# car_key.net
KiCad netlist of a schematic drawn in EAGLE
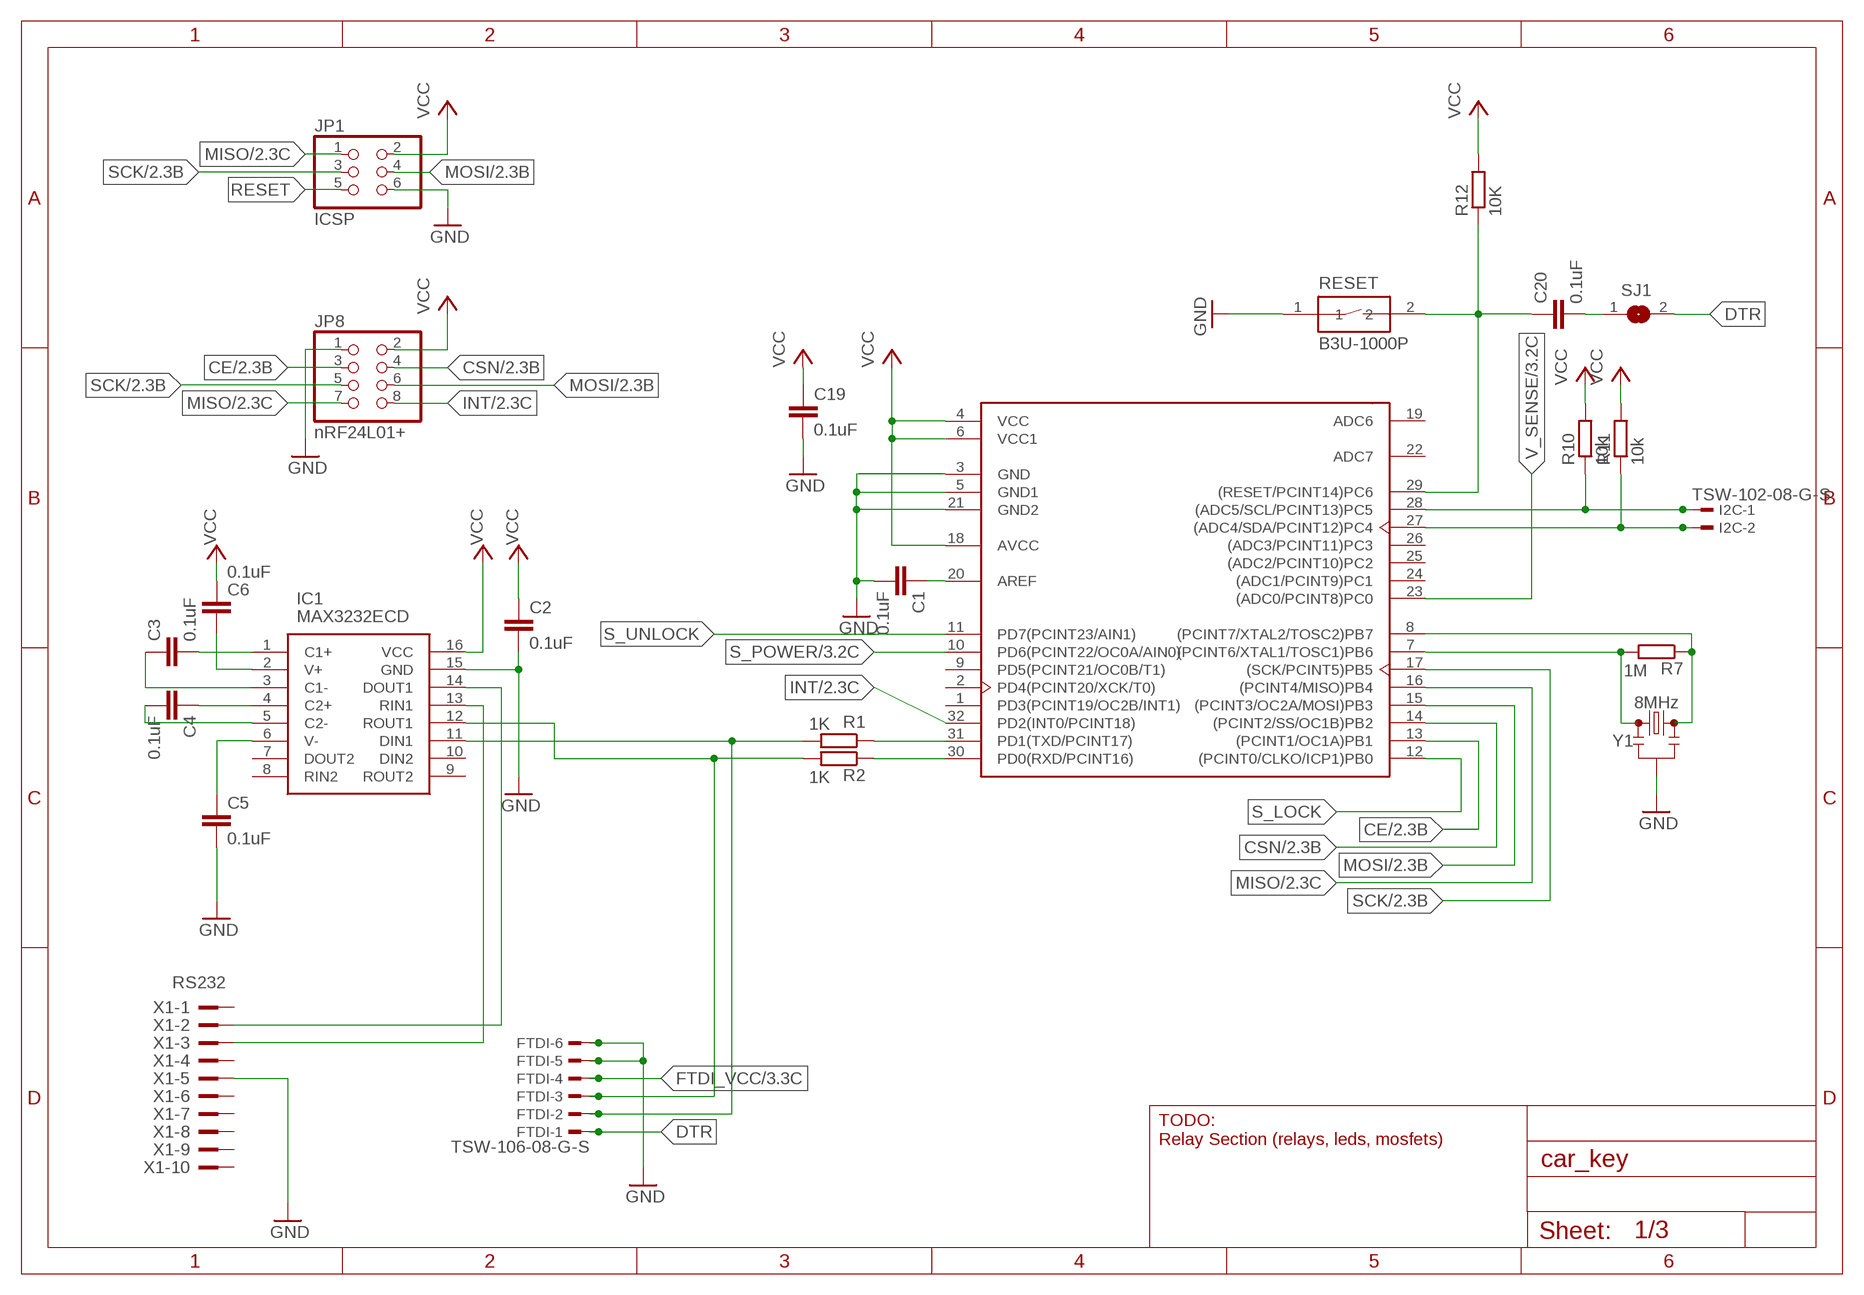
[diagram p0: schematic, sheet 1]
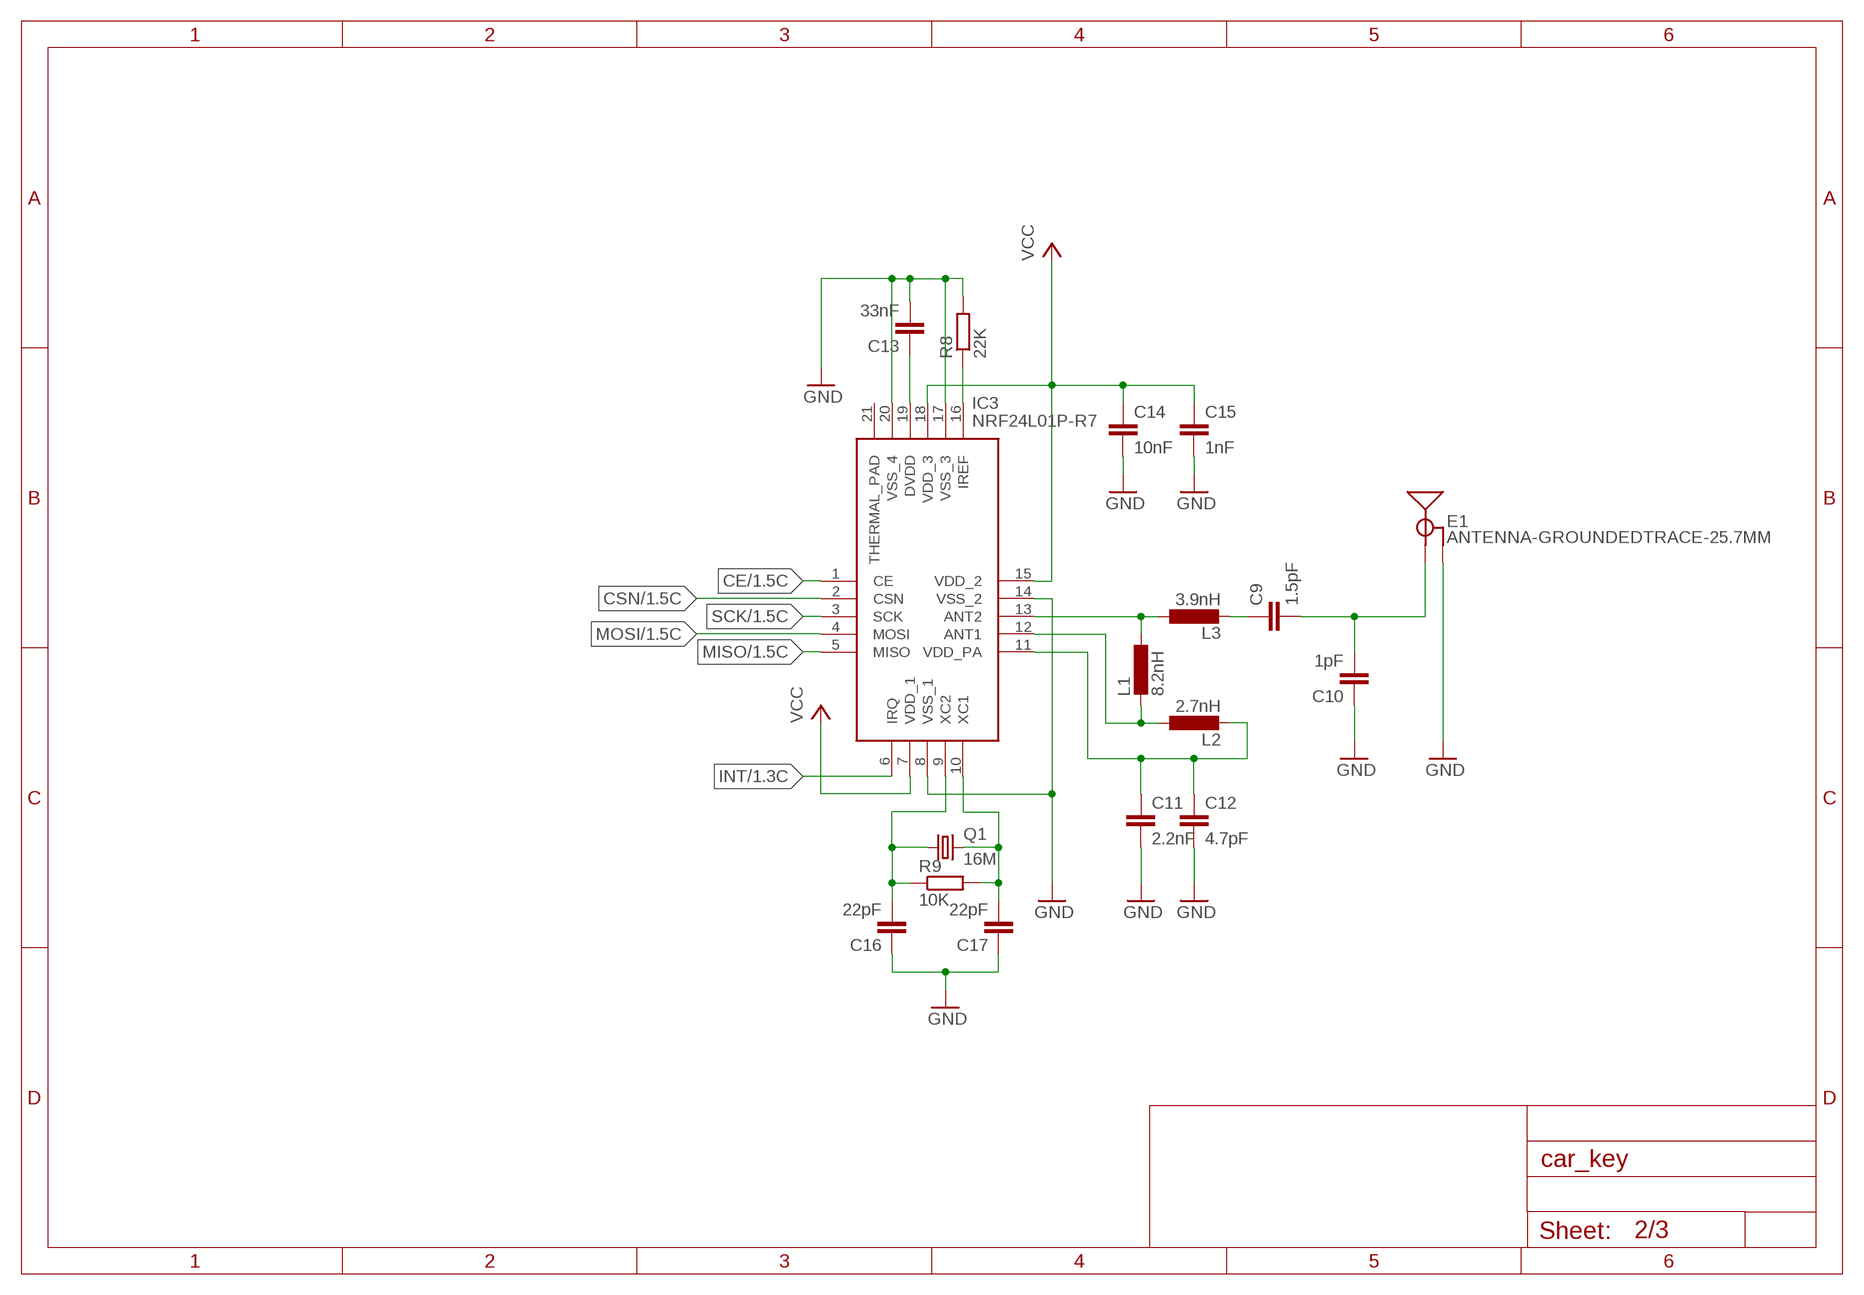
[diagram p1: schematic, sheet 2]
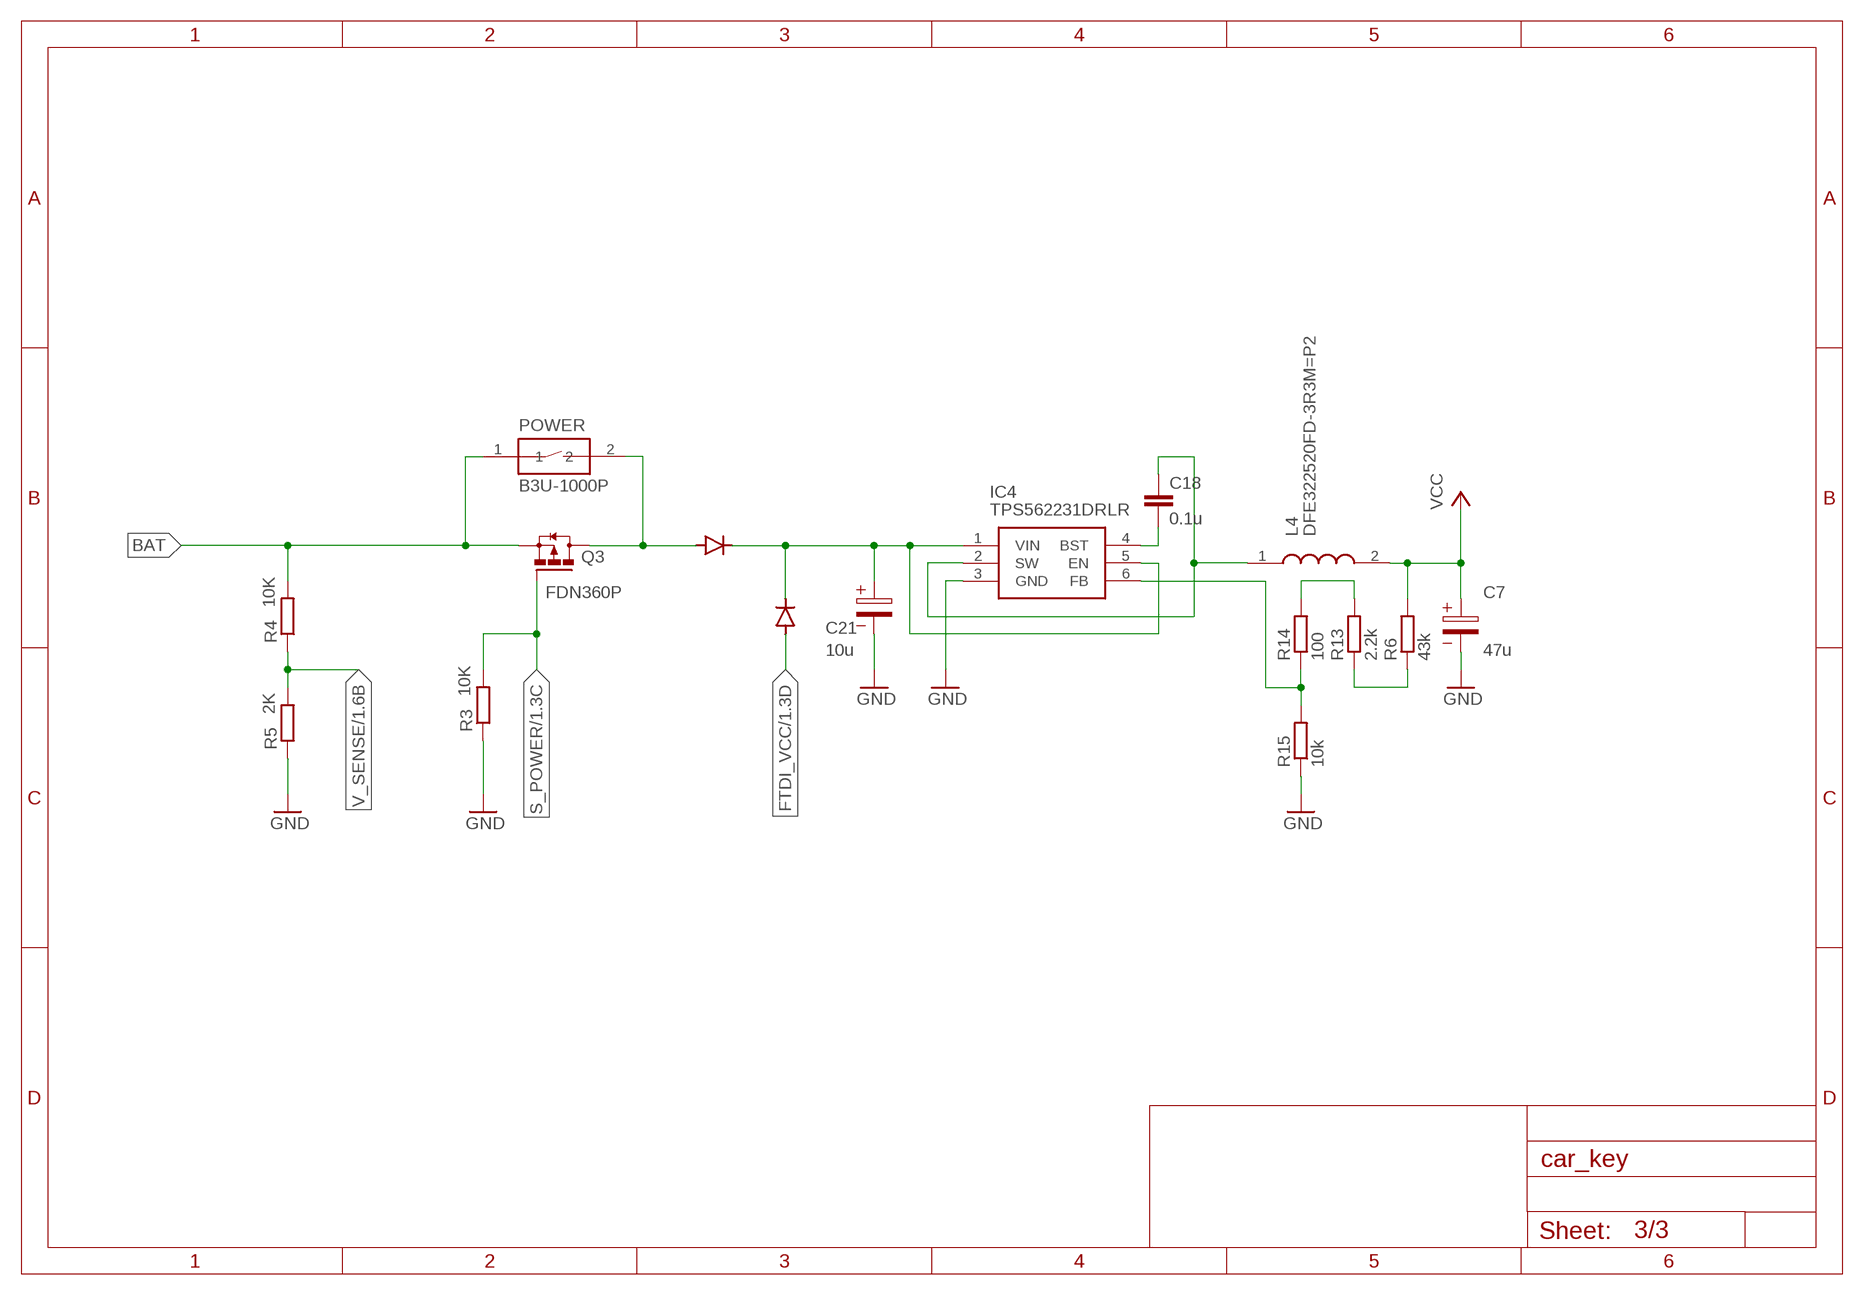
[diagram p2: schematic, sheet 3]

(export (version "E")
  (design (tool "Eeschema 10.0.6"))
  (components
    (comp (ref "C9")
      (value "1.5pF")
      (footprint "eagle-import:C0805")
      (libsource (lib "eagle-import") (part "resistor_348_C-EUC0805"))
    )
    (comp (ref "C10")
      (value "1pF")
      (footprint "eagle-import:C0805")
      (libsource (lib "eagle-import") (part "resistor_348_C-EUC0805"))
    )
    (comp (ref "C11")
      (value "2.2nF")
      (footprint "eagle-import:C0805")
      (libsource (lib "eagle-import") (part "resistor_348_C-EUC0805"))
    )
    (comp (ref "C12")
      (value "4.7pF")
      (footprint "eagle-import:C0805")
      (libsource (lib "eagle-import") (part "resistor_348_C-EUC0805"))
    )
    (comp (ref "C13")
      (value "33nF")
      (footprint "eagle-import:C0805")
      (libsource (lib "eagle-import") (part "resistor_348_C-EUC0805"))
    )
    (comp (ref "C14")
      (value "10nF")
      (footprint "eagle-import:C0805")
      (libsource (lib "eagle-import") (part "resistor_348_C-EUC0805"))
    )
    (comp (ref "C15")
      (value "1nF")
      (footprint "eagle-import:C0805")
      (libsource (lib "eagle-import") (part "resistor_348_C-EUC0805"))
    )
    (comp (ref "C16")
      (value "22pF")
      (footprint "eagle-import:C0805")
      (libsource (lib "eagle-import") (part "resistor_348_C-EUC0805"))
    )
    (comp (ref "C17")
      (value "22pF")
      (footprint "eagle-import:C0805")
      (libsource (lib "eagle-import") (part "resistor_348_C-EUC0805"))
    )
    (comp (ref "E1")
      (value "ANTENNA-GROUNDEDTRACE-25.7MM")
      (footprint "eagle-import:TRACE_ANTENNA_2.4GHZ_25.7MM")
      (libsource (lib "eagle-import") (part "ANTENNA-GROUNDEDTRACE-25.7MM"))
    )
    (comp (ref "IC3")
      (value "NRF24L01P-R7")
      (footprint "eagle-import:QFN50P400X400X95-21N")
      (fields (field (name "MOUSER_PART_NUMBER") "949-NRF24L01P-R7"))
      (libsource (lib "eagle-import") (part "NRF24L01P-R7"))
    )
    (comp (ref "L1")
      (value "8.2nH")
      (footprint "eagle-import:L2012C")
      (libsource (lib "eagle-import") (part "L-EUL2012C"))
    )
    (comp (ref "L2")
      (value "2.7nH")
      (footprint "eagle-import:L2012C")
      (libsource (lib "eagle-import") (part "L-EUL2012C"))
    )
    (comp (ref "L3")
      (value "3.9nH")
      (footprint "eagle-import:L2012C")
      (libsource (lib "eagle-import") (part "L-EUL2012C"))
    )
    (comp (ref "Q1")
      (value "16M")
      (footprint "eagle-import:HC49_S")
      (libsource (lib "eagle-import") (part "CRYSTALHC49S"))
    )
    (comp (ref "R8")
      (value "22K")
      (footprint "eagle-import:R0805")
      (libsource (lib "eagle-import") (part "R-EU_R0805"))
    )
    (comp (ref "R9")
      (value "10K")
      (footprint "eagle-import:R0805")
      (libsource (lib "eagle-import") (part "R-EU_R0805"))
    )
    (comp (ref "C1")
      (value "0.1uF")
      (footprint "eagle-import:C0805")
      (libsource (lib "eagle-import") (part "C-EUC0805"))
    )
    (comp (ref "C2")
      (value "0.1uF")
      (footprint "eagle-import:C0805")
      (libsource (lib "eagle-import") (part "C-EUC0805"))
    )
    (comp (ref "C3")
      (value "0.1uF")
      (footprint "eagle-import:C0805")
      (libsource (lib "eagle-import") (part "C-EUC0805"))
    )
    (comp (ref "C4")
      (value "0.1uF")
      (footprint "eagle-import:C0805")
      (libsource (lib "eagle-import") (part "C-EUC0805"))
    )
    (comp (ref "C5")
      (value "0.1uF")
      (footprint "eagle-import:C0805")
      (libsource (lib "eagle-import") (part "C-EUC0805"))
    )
    (comp (ref "C6")
      (value "0.1uF")
      (footprint "eagle-import:C0805")
      (libsource (lib "eagle-import") (part "C-EUC0805"))
    )
    (comp (ref "C19")
      (value "0.1uF")
      (footprint "eagle-import:C0805")
      (libsource (lib "eagle-import") (part "C-EUC0805"))
    )
    (comp (ref "C20")
      (value "0.1uF")
      (footprint "eagle-import:C0805")
      (libsource (lib "eagle-import") (part "C-EUC0805"))
    )
    (comp (ref "FTDI")
      (value "TSW-106-08-G-S")
      (footprint "eagle-import:TSW-106-XX-G-S")
      (fields (field (name "MF") "Samtec Inc.") (field (name "MPN") "TSW-106-07-G-S"))
      (libsource (lib "eagle-import") (part "TSW-106--G-S08"))
    )
    (comp (ref "I2C")
      (value "TSW-102-08-G-S")
      (footprint "eagle-import:TSW-102-XX-G-S")
      (fields (field (name "MF") "Samtec Inc.") (field (name "MPN") "TSW-102-07-G-S"))
      (libsource (lib "eagle-import") (part "TSW-102--G-S08"))
    )
    (comp (ref "IC1")
      (value "MAX3232ECD")
      (footprint "eagle-import:SOIC127P600X175-16N")
      (fields (field (name "MOUSER_PART_NUMBER") "595-MAX3232ECD") (field (name "RS_PART_NUMBER") "6608704P"))
      (libsource (lib "eagle-import") (part "MAX3232ECD"))
    )
    (comp (ref "JP1")
      (value "ICSP")
      (footprint "eagle-import:2X03")
      (libsource (lib "eagle-import") (part "PINHD-2X3"))
    )
    (comp (ref "JP8")
      (value "nRF24L01+")
      (footprint "eagle-import:2X04")
      (libsource (lib "eagle-import") (part "PINHD-2X4"))
    )
    (comp (ref "R1")
      (value "1K")
      (footprint "eagle-import:R0805")
      (libsource (lib "eagle-import") (part "R-EU_R0805"))
    )
    (comp (ref "R2")
      (value "1K")
      (footprint "eagle-import:R0805")
      (libsource (lib "eagle-import") (part "R-EU_R0805"))
    )
    (comp (ref "R7")
      (value "1M")
      (footprint "eagle-import:R0805")
      (libsource (lib "eagle-import") (part "R-EU_R0805"))
    )
    (comp (ref "R10")
      (value "10k")
      (footprint "eagle-import:R0805")
      (libsource (lib "eagle-import") (part "R-EU_R0805"))
    )
    (comp (ref "R11")
      (value "10k")
      (footprint "eagle-import:R0805")
      (libsource (lib "eagle-import") (part "R-EU_R0805"))
    )
    (comp (ref "R12")
      (value "10K")
      (footprint "eagle-import:R0805")
      (libsource (lib "eagle-import") (part "R-EU_R0805"))
    )
    (comp (ref "RESET")
      (value "B3U-1000P")
      (footprint "eagle-import:B3U-1000P")
      (fields
        (field (name "DIGI_KEY_PART_NUMBER") "SW1020CT-ND")
        (field (name "MANUFACTURER") "Omron Electronics Inc-EMC Div")
        (field (name "CREATED_BY") "PCBLayout.com")
      )
      (libsource (lib "eagle-import") (part "B3U-1000P"))
    )
    (comp (ref "SJ1") (value "SJ") (footprint "eagle-import:SJ") (libsource (lib "eagle-import") (part "SJ")))
    (comp (ref "U2")
      (value "ATMEGA328P-AU")
      (footprint "eagle-import:TQFP-32")
      (fields
        (field (name "DIGIKEY_PART_NUMBER") "ATMEGA328P-AU-ND")
        (field (name "MANUFACTURER") "Microchip Technology")
        (field (name "CREATED_BY") "PCBLayout.com")
      )
      (libsource (lib "eagle-import") (part "ATMEGA328P-AU"))
    )
    (comp (ref "X1")
      (value "RS232")
      (footprint "eagle-import:PAK100_2500-10")
      (fields (field (name "MF") "3M") (field (name "MPN") "2510-6002UB"))
      (libsource (lib "eagle-import") (part "2510-"))
    )
    (comp (ref "Y1")
      (value "8MHz")
      (footprint "eagle-import:RESONATOR-SMD-3.2X1.3")
      (libsource (lib "eagle-import") (part "RESONATOR-8MHZSMD_3.2X1.3"))
    )
    (comp (ref "C7")
      (value "47u")
      (footprint "eagle-import:2.6X1.6X1(BXCXA)")
      (libsource (lib "eagle-import") (part "WCAP-ASLI_865080140004_4X5,5"))
    )
    (comp (ref "C18")
      (value "0.1u")
      (footprint "eagle-import:C0805")
      (libsource (lib "eagle-import") (part "C-EUC0805"))
    )
    (comp (ref "C21")
      (value "10u")
      (footprint "eagle-import:2.6X1.6X1(BXCXA)")
      (libsource (lib "eagle-import") (part "WCAP-ASLI_865080340001_4X5,5"))
    )
    (comp (ref "D1")
      (value "DIODE-SOD123")
      (footprint "eagle-import:SOD123")
      (libsource (lib "eagle-import") (part "DIODE-SOD123"))
    )
    (comp (ref "D2")
      (value "DIODE-SOD123")
      (footprint "eagle-import:SOD123")
      (libsource (lib "eagle-import") (part "DIODE-SOD123"))
    )
    (comp (ref "IC4")
      (value "TPS562231DRLR")
      (footprint "eagle-import:SOTFL50P160X60-6N")
      (fields (field (name "MOUSER_PART_NUMBER") "595-TPS562231DRLR"))
      (libsource (lib "eagle-import") (part "TPS562231DRLR"))
    )
    (comp (ref "L4")
      (value "DFE322520FD-3R3M=P2")
      (footprint "eagle-import:INDC3225X200N")
      (fields (field (name "MOUSER_PART_NUMBER") "81-DFE322520FD3R3MP2"))
      (libsource (lib "eagle-import") (part "DFE322520FD-3R3M=P2"))
    )
    (comp (ref "POWER")
      (value "B3U-1000P")
      (footprint "eagle-import:B3U-1000P")
      (fields
        (field (name "DIGI_KEY_PART_NUMBER") "SW1020CT-ND")
        (field (name "MANUFACTURER") "Omron Electronics Inc-EMC Div")
        (field (name "CREATED_BY") "PCBLayout.com")
      )
      (libsource (lib "eagle-import") (part "B3U-1000P"))
    )
    (comp (ref "Q3")
      (value "FDN360P")
      (footprint "eagle-import:SUPER-SOT3")
      (libsource (lib "eagle-import") (part "FDN360P"))
    )
    (comp (ref "R3")
      (value "10K")
      (footprint "eagle-import:R0805")
      (libsource (lib "eagle-import") (part "R-EU_R0805"))
    )
    (comp (ref "R4")
      (value "10K")
      (footprint "eagle-import:R0805")
      (libsource (lib "eagle-import") (part "R-EU_R0805"))
    )
    (comp (ref "R5")
      (value "2K")
      (footprint "eagle-import:R0805")
      (libsource (lib "eagle-import") (part "R-EU_R0805"))
    )
    (comp (ref "R6")
      (value "43k")
      (footprint "eagle-import:R0805")
      (libsource (lib "eagle-import") (part "R-EU_R0805"))
    )
    (comp (ref "R13")
      (value "2.2k")
      (footprint "eagle-import:R0805")
      (libsource (lib "eagle-import") (part "R-EU_R0805"))
    )
    (comp (ref "R14")
      (value "100")
      (footprint "eagle-import:R0805")
      (libsource (lib "eagle-import") (part "R-EU_R0805"))
    )
    (comp (ref "R15")
      (value "10k")
      (footprint "eagle-import:R0805")
      (libsource (lib "eagle-import") (part "R-EU_R0805"))
    )
  )
  (nets
    (net (code "1") (name "BAT") (class "Default")
      (node (ref "POWER") (pin "1") (pinfunction "1_1") (pintype "passive"))
      (node (ref "Q3") (pin "2") (pinfunction "S_2") (pintype "passive"))
      (node (ref "R4") (pin "2") (pinfunction "2_2") (pintype "passive"))
    )
    (net (code "2") (name "CE") (class "Default")
      (node (ref "IC3") (pin "1") (pinfunction "CE_1") (pintype "bidirectional"))
      (node (ref "JP8") (pin "3") (pinfunction "3_3") (pintype "passive"))
      (node (ref "U2") (pin "13") (pinfunction "(PCINT1/OC1A)PB1_13") (pintype "bidirectional"))
    )
    (net (code "3") (name "CSN") (class "Default")
      (node (ref "IC3") (pin "2") (pinfunction "CSN_2") (pintype "bidirectional"))
      (node (ref "JP8") (pin "4") (pinfunction "4_4") (pintype "passive"))
      (node (ref "U2") (pin "14") (pinfunction "(PCINT2/SS/OC1B)PB2_14") (pintype "bidirectional"))
    )
    (net (code "4") (name "DTR") (class "Default")
      (node (ref "FTDI") (pin "1") (pinfunction "1_1") (pintype "passive"))
      (node (ref "SJ1") (pin "2") (pinfunction "2_2") (pintype "passive"))
    )
    (net (code "5") (name "FTDI_VCC") (class "Default")
      (node (ref "D1") (pin "A") (pinfunction "A_A") (pintype "passive"))
      (node (ref "FTDI") (pin "4") (pinfunction "1_4") (pintype "passive"))
    )
    (net (code "6") (name "GND") (class "Default")
      (node (ref "C1") (pin "2") (pinfunction "2_2") (pintype "passive"))
      (node (ref "C10") (pin "1") (pinfunction "1_1") (pintype "passive"))
      (node (ref "C11") (pin "2") (pinfunction "2_2") (pintype "passive"))
      (node (ref "C12") (pin "2") (pinfunction "2_2") (pintype "passive"))
      (node (ref "C13") (pin "2") (pinfunction "2_2") (pintype "passive"))
      (node (ref "C14") (pin "2") (pinfunction "2_2") (pintype "passive"))
      (node (ref "C15") (pin "2") (pinfunction "2_2") (pintype "passive"))
      (node (ref "C16") (pin "1") (pinfunction "1_1") (pintype "passive"))
      (node (ref "C17") (pin "1") (pinfunction "1_1") (pintype "passive"))
      (node (ref "C19") (pin "2") (pinfunction "2_2") (pintype "passive"))
      (node (ref "C2") (pin "2") (pinfunction "2_2") (pintype "passive"))
      (node (ref "C21") (pin "2") (pinfunction "2_2") (pintype "passive"))
      (node (ref "C5") (pin "2") (pinfunction "2_2") (pintype "passive"))
      (node (ref "C7") (pin "2") (pinfunction "2_2") (pintype "passive"))
      (node (ref "E1") (pin "GND") (pinfunction "GND_GND") (pintype "bidirectional"))
      (node (ref "E1") (pin "GND2") (pinfunction "GND_GND2") (pintype "bidirectional"))
      (node (ref "FTDI") (pin "5") (pinfunction "1_5") (pintype "passive"))
      (node (ref "FTDI") (pin "6") (pinfunction "1_6") (pintype "passive"))
      (node (ref "IC1") (pin "15") (pinfunction "GND_15") (pintype "bidirectional"))
      (node (ref "IC3") (pin "14") (pinfunction "VSS_2_14") (pintype "bidirectional"))
      (node (ref "IC3") (pin "17") (pinfunction "VSS_3_17") (pintype "bidirectional"))
      (node (ref "IC3") (pin "20") (pinfunction "VSS_4_20") (pintype "bidirectional"))
      (node (ref "IC3") (pin "8") (pinfunction "VSS_1_8") (pintype "bidirectional"))
      (node (ref "IC4") (pin "3") (pinfunction "GND_3") (pintype "bidirectional"))
      (node (ref "JP1") (pin "6") (pinfunction "6_6") (pintype "passive"))
      (node (ref "JP8") (pin "1") (pinfunction "1_1") (pintype "passive"))
      (node (ref "R15") (pin "1") (pinfunction "1_1") (pintype "passive"))
      (node (ref "R3") (pin "1") (pinfunction "1_1") (pintype "passive"))
      (node (ref "R5") (pin "1") (pinfunction "1_1") (pintype "passive"))
      (node (ref "R8") (pin "2") (pinfunction "2_2") (pintype "passive"))
      (node (ref "RESET") (pin "1") (pinfunction "1_1") (pintype "passive"))
      (node (ref "U2") (pin "21") (pinfunction "GND2_21") (pintype "power_in"))
      (node (ref "U2") (pin "3") (pinfunction "GND_3") (pintype "power_in"))
      (node (ref "U2") (pin "5") (pinfunction "GND1_5") (pintype "power_in"))
      (node (ref "X1") (pin "5") (pinfunction "KL_5") (pintype "passive"))
      (node (ref "Y1") (pin "2") (pinfunction "2_2") (pintype "passive"))
    )
    (net (code "7") (name "INT") (class "Default")
      (node (ref "IC3") (pin "6") (pinfunction "IRQ_6") (pintype "bidirectional"))
      (node (ref "JP8") (pin "8") (pinfunction "8_8") (pintype "passive"))
      (node (ref "U2") (pin "32") (pinfunction "PD2(INT0/PCINT18)_32") (pintype "bidirectional"))
    )
    (net (code "8") (name "MISO") (class "Default")
      (node (ref "IC3") (pin "5") (pinfunction "MISO_5") (pintype "bidirectional"))
      (node (ref "JP1") (pin "1") (pinfunction "1_1") (pintype "passive"))
      (node (ref "JP8") (pin "7") (pinfunction "7_7") (pintype "passive"))
      (node (ref "U2") (pin "16") (pinfunction "(PCINT4/MISO)PB4_16") (pintype "bidirectional"))
    )
    (net (code "9") (name "MOSI") (class "Default")
      (node (ref "IC3") (pin "4") (pinfunction "MOSI_4") (pintype "bidirectional"))
      (node (ref "JP1") (pin "4") (pinfunction "4_4") (pintype "passive"))
      (node (ref "JP8") (pin "6") (pinfunction "6_6") (pintype "passive"))
      (node (ref "U2") (pin "15") (pinfunction "(PCINT3/OC2A/MOSI)PB3_15") (pintype "bidirectional"))
    )
    (net (code "10") (name "Net-(C9-Pad1)") (class "Default")
      (node (ref "C9") (pin "1") (pinfunction "1_1") (pintype "passive"))
      (node (ref "L3") (pin "2") (pinfunction "2_2") (pintype "passive"))
    )
    (net (code "11") (name "Net-(C20-Pad2)") (class "Default")
      (node (ref "C20") (pin "2") (pinfunction "2_2") (pintype "passive"))
      (node (ref "SJ1") (pin "1") (pinfunction "1_1") (pintype "passive"))
    )
    (net (code "12") (name "Net-(E1-SIGNAL)") (class "Default")
      (node (ref "C10") (pin "2") (pinfunction "2_2") (pintype "passive"))
      (node (ref "C9") (pin "2") (pinfunction "2_2") (pintype "passive"))
      (node (ref "E1") (pin "ANT") (pinfunction "SIGNAL_ANT") (pintype "bidirectional"))
    )
    (net (code "13") (name "Net-(FTDIB-1)") (class "Default")
      (node (ref "FTDI") (pin "2") (pinfunction "1_2") (pintype "passive"))
      (node (ref "IC1") (pin "11") (pinfunction "DIN1_11") (pintype "bidirectional"))
      (node (ref "R1") (pin "2") (pinfunction "2_2") (pintype "passive"))
    )
    (net (code "14") (name "Net-(FTDIC-1)") (class "Default")
      (node (ref "FTDI") (pin "3") (pinfunction "1_3") (pintype "passive"))
      (node (ref "IC1") (pin "12") (pinfunction "ROUT1_12") (pintype "bidirectional"))
      (node (ref "R2") (pin "2") (pinfunction "2_2") (pintype "passive"))
    )
    (net (code "15") (name "Net-(I2CB-1)") (class "Default")
      (node (ref "I2C") (pin "2") (pinfunction "1_2") (pintype "passive"))
      (node (ref "R11") (pin "1") (pinfunction "1_1") (pintype "passive"))
      (node (ref "U2") (pin "27") (pinfunction "(ADC4/SDA/PCINT12)PC4_27") (pintype "bidirectional"))
    )
    (net (code "16") (name "Net-(IC1-C1+)") (class "Default")
      (node (ref "C3") (pin "2") (pinfunction "2_2") (pintype "passive"))
      (node (ref "IC1") (pin "1") (pinfunction "C1+_1") (pintype "bidirectional"))
    )
    (net (code "17") (name "Net-(IC1-C1-)") (class "Default")
      (node (ref "C3") (pin "1") (pinfunction "1_1") (pintype "passive"))
      (node (ref "IC1") (pin "3") (pinfunction "C1-_3") (pintype "bidirectional"))
    )
    (net (code "18") (name "Net-(IC1-C2+)") (class "Default")
      (node (ref "C4") (pin "1") (pinfunction "1_1") (pintype "passive"))
      (node (ref "IC1") (pin "4") (pinfunction "C2+_4") (pintype "bidirectional"))
    )
    (net (code "19") (name "Net-(IC1-C2-)") (class "Default")
      (node (ref "C4") (pin "2") (pinfunction "2_2") (pintype "passive"))
      (node (ref "IC1") (pin "5") (pinfunction "C2-_5") (pintype "bidirectional"))
    )
    (net (code "20") (name "Net-(IC1-DOUT1)") (class "Default")
      (node (ref "IC1") (pin "14") (pinfunction "DOUT1_14") (pintype "bidirectional"))
      (node (ref "X1") (pin "2") (pinfunction "KL_2") (pintype "passive"))
    )
    (net (code "21") (name "Net-(IC1-RIN1)") (class "Default")
      (node (ref "IC1") (pin "13") (pinfunction "RIN1_13") (pintype "bidirectional"))
      (node (ref "X1") (pin "3") (pinfunction "KL_3") (pintype "passive"))
    )
    (net (code "22") (name "Net-(IC1-V+)") (class "Default")
      (node (ref "C6") (pin "1") (pinfunction "1_1") (pintype "passive"))
      (node (ref "IC1") (pin "2") (pinfunction "V+_2") (pintype "bidirectional"))
    )
    (net (code "23") (name "Net-(IC1-V-)") (class "Default")
      (node (ref "C5") (pin "1") (pinfunction "1_1") (pintype "passive"))
      (node (ref "IC1") (pin "6") (pinfunction "V-_6") (pintype "bidirectional"))
    )
    (net (code "24") (name "Net-(IC3-ANT1)") (class "Default")
      (node (ref "IC3") (pin "12") (pinfunction "ANT1_12") (pintype "bidirectional"))
      (node (ref "L1") (pin "2") (pinfunction "2_2") (pintype "passive"))
      (node (ref "L2") (pin "1") (pinfunction "1_1") (pintype "passive"))
    )
    (net (code "25") (name "Net-(IC3-ANT2)") (class "Default")
      (node (ref "IC3") (pin "13") (pinfunction "ANT2_13") (pintype "bidirectional"))
      (node (ref "L1") (pin "1") (pinfunction "1_1") (pintype "passive"))
      (node (ref "L3") (pin "1") (pinfunction "1_1") (pintype "passive"))
    )
    (net (code "26") (name "Net-(IC3-DVDD)") (class "Default")
      (node (ref "C13") (pin "1") (pinfunction "1_1") (pintype "passive"))
      (node (ref "IC3") (pin "19") (pinfunction "DVDD_19") (pintype "bidirectional"))
    )
    (net (code "27") (name "Net-(IC3-IREF)") (class "Default")
      (node (ref "IC3") (pin "16") (pinfunction "IREF_16") (pintype "bidirectional"))
      (node (ref "R8") (pin "1") (pinfunction "1_1") (pintype "passive"))
    )
    (net (code "28") (name "Net-(IC3-VDD_PA)") (class "Default")
      (node (ref "C11") (pin "1") (pinfunction "1_1") (pintype "passive"))
      (node (ref "C12") (pin "1") (pinfunction "1_1") (pintype "passive"))
      (node (ref "IC3") (pin "11") (pinfunction "VDD_PA_11") (pintype "bidirectional"))
      (node (ref "L2") (pin "2") (pinfunction "2_2") (pintype "passive"))
    )
    (net (code "29") (name "Net-(IC3-XC1)") (class "Default")
      (node (ref "C17") (pin "2") (pinfunction "2_2") (pintype "passive"))
      (node (ref "IC3") (pin "10") (pinfunction "XC1_10") (pintype "bidirectional"))
      (node (ref "Q1") (pin "2") (pinfunction "2_2") (pintype "passive"))
      (node (ref "R9") (pin "2") (pinfunction "2_2") (pintype "passive"))
    )
    (net (code "30") (name "Net-(IC3-XC2)") (class "Default")
      (node (ref "C16") (pin "2") (pinfunction "2_2") (pintype "passive"))
      (node (ref "IC3") (pin "9") (pinfunction "XC2_9") (pintype "bidirectional"))
      (node (ref "Q1") (pin "1") (pinfunction "1_1") (pintype "passive"))
      (node (ref "R9") (pin "1") (pinfunction "1_1") (pintype "passive"))
    )
    (net (code "31") (name "Net-(IC4-BST)") (class "Default")
      (node (ref "C18") (pin "2") (pinfunction "2_2") (pintype "passive"))
      (node (ref "IC4") (pin "4") (pinfunction "BST_4") (pintype "bidirectional"))
    )
    (net (code "32") (name "Net-(IC4-EN)") (class "Default")
      (node (ref "C21") (pin "1") (pinfunction "1_1") (pintype "passive"))
      (node (ref "D1") (pin "C") (pinfunction "C_C") (pintype "passive"))
      (node (ref "D2") (pin "C") (pinfunction "C_C") (pintype "passive"))
      (node (ref "IC4") (pin "1") (pinfunction "VIN_1") (pintype "bidirectional"))
      (node (ref "IC4") (pin "5") (pinfunction "EN_5") (pintype "bidirectional"))
    )
    (net (code "33") (name "Net-(IC4-FB)") (class "Default")
      (node (ref "IC4") (pin "6") (pinfunction "FB_6") (pintype "bidirectional"))
      (node (ref "R14") (pin "1") (pinfunction "1_1") (pintype "passive"))
      (node (ref "R15") (pin "2") (pinfunction "2_2") (pintype "passive"))
    )
    (net (code "34") (name "Net-(IC4-SW)") (class "Default")
      (node (ref "C18") (pin "1") (pinfunction "1_1") (pintype "passive"))
      (node (ref "IC4") (pin "2") (pinfunction "SW_2") (pintype "bidirectional"))
      (node (ref "L4") (pin "1") (pinfunction "1_1") (pintype "bidirectional"))
    )
    (net (code "35") (name "Net-(Q3-D)") (class "Default")
      (node (ref "D2") (pin "A") (pinfunction "A_A") (pintype "passive"))
      (node (ref "POWER") (pin "2") (pinfunction "2_2") (pintype "passive"))
      (node (ref "Q3") (pin "3") (pinfunction "D_3") (pintype "passive"))
    )
    (net (code "36") (name "Net-(R13-Pad1)") (class "Default")
      (node (ref "R13") (pin "1") (pinfunction "1_1") (pintype "passive"))
      (node (ref "R6") (pin "1") (pinfunction "1_1") (pintype "passive"))
    )
    (net (code "37") (name "Net-(R13-Pad2)") (class "Default")
      (node (ref "R13") (pin "2") (pinfunction "2_2") (pintype "passive"))
      (node (ref "R14") (pin "2") (pinfunction "2_2") (pintype "passive"))
    )
    (net (code "38") (name "Net-(U2-(ADC5{slash}SCL{slash}PCINT13)PC5)") (class "Default")
      (node (ref "I2C") (pin "1") (pinfunction "1_1") (pintype "passive"))
      (node (ref "R10") (pin "1") (pinfunction "1_1") (pintype "passive"))
      (node (ref "U2") (pin "28") (pinfunction "(ADC5/SCL/PCINT13)PC5_28") (pintype "bidirectional"))
    )
    (net (code "39") (name "Net-(U2-(PCINT6{slash}XTAL1{slash}TOSC1)PB6)") (class "Default")
      (node (ref "R7") (pin "2") (pinfunction "2_2") (pintype "passive"))
      (node (ref "U2") (pin "7") (pinfunction "(PCINT6/XTAL1/TOSC1)PB6_7") (pintype "bidirectional"))
      (node (ref "Y1") (pin "1") (pinfunction "1_1") (pintype "passive"))
    )
    (net (code "40") (name "Net-(U2-(PCINT7{slash}XTAL2{slash}TOSC2)PB7)") (class "Default")
      (node (ref "R7") (pin "1") (pinfunction "1_1") (pintype "passive"))
      (node (ref "U2") (pin "8") (pinfunction "(PCINT7/XTAL2/TOSC2)PB7_8") (pintype "bidirectional"))
      (node (ref "Y1") (pin "3") (pinfunction "3_3") (pintype "passive"))
    )
    (net (code "41") (name "Net-(U2-AREF)") (class "Default")
      (node (ref "C1") (pin "1") (pinfunction "1_1") (pintype "passive"))
      (node (ref "U2") (pin "20") (pinfunction "AREF_20") (pintype "power_in"))
    )
    (net (code "42") (name "Net-(U2-PD0(RXD{slash}PCINT16))") (class "Default")
      (node (ref "R2") (pin "1") (pinfunction "1_1") (pintype "passive"))
      (node (ref "U2") (pin "30") (pinfunction "PD0(RXD/PCINT16)_30") (pintype "bidirectional"))
    )
    (net (code "43") (name "Net-(U2-PD1(TXD{slash}PCINT17))") (class "Default")
      (node (ref "R1") (pin "1") (pinfunction "1_1") (pintype "passive"))
      (node (ref "U2") (pin "31") (pinfunction "PD1(TXD/PCINT17)_31") (pintype "bidirectional"))
    )
    (net (code "44") (name "RESET") (class "Default")
      (node (ref "C20") (pin "1") (pinfunction "1_1") (pintype "passive"))
      (node (ref "JP1") (pin "5") (pinfunction "5_5") (pintype "passive"))
      (node (ref "R12") (pin "1") (pinfunction "1_1") (pintype "passive"))
      (node (ref "RESET") (pin "2") (pinfunction "2_2") (pintype "passive"))
      (node (ref "U2") (pin "29") (pinfunction "(RESET/PCINT14)PC6_29") (pintype "bidirectional"))
    )
    (net (code "45") (name "SCK") (class "Default")
      (node (ref "IC3") (pin "3") (pinfunction "SCK_3") (pintype "bidirectional"))
      (node (ref "JP1") (pin "3") (pinfunction "3_3") (pintype "passive"))
      (node (ref "JP8") (pin "5") (pinfunction "5_5") (pintype "passive"))
      (node (ref "U2") (pin "17") (pinfunction "(SCK/PCINT5)PB5_17") (pintype "bidirectional"))
    )
    (net (code "46") (name "S_LOCK") (class "Default")
      (node (ref "U2") (pin "12") (pinfunction "(PCINT0/CLKO/ICP1)PB0_12") (pintype "bidirectional"))
    )
    (net (code "47") (name "S_POWER") (class "Default")
      (node (ref "Q3") (pin "1") (pinfunction "G_1") (pintype "passive"))
      (node (ref "R3") (pin "2") (pinfunction "2_2") (pintype "passive"))
      (node (ref "U2") (pin "10") (pinfunction "PD6(PCINT22/OC0A/AIN0)_10") (pintype "bidirectional"))
    )
    (net (code "48") (name "S_UNLOCK") (class "Default")
      (node (ref "U2") (pin "11") (pinfunction "PD7(PCINT23/AIN1)_11") (pintype "bidirectional"))
    )
    (net (code "49") (name "VCC") (class "Default")
      (node (ref "C14") (pin "1") (pinfunction "1_1") (pintype "passive"))
      (node (ref "C15") (pin "1") (pinfunction "1_1") (pintype "passive"))
      (node (ref "C19") (pin "1") (pinfunction "1_1") (pintype "passive"))
      (node (ref "C2") (pin "1") (pinfunction "1_1") (pintype "passive"))
      (node (ref "C6") (pin "2") (pinfunction "2_2") (pintype "passive"))
      (node (ref "C7") (pin "1") (pinfunction "1_1") (pintype "passive"))
      (node (ref "IC1") (pin "16") (pinfunction "VCC_16") (pintype "bidirectional"))
      (node (ref "IC3") (pin "15") (pinfunction "VDD_2_15") (pintype "bidirectional"))
      (node (ref "IC3") (pin "18") (pinfunction "VDD_3_18") (pintype "bidirectional"))
      (node (ref "IC3") (pin "7") (pinfunction "VDD_1_7") (pintype "bidirectional"))
      (node (ref "JP1") (pin "2") (pinfunction "2_2") (pintype "passive"))
      (node (ref "JP8") (pin "2") (pinfunction "2_2") (pintype "passive"))
      (node (ref "L4") (pin "2") (pinfunction "2_2") (pintype "bidirectional"))
      (node (ref "R10") (pin "2") (pinfunction "2_2") (pintype "passive"))
      (node (ref "R11") (pin "2") (pinfunction "2_2") (pintype "passive"))
      (node (ref "R12") (pin "2") (pinfunction "2_2") (pintype "passive"))
      (node (ref "R6") (pin "2") (pinfunction "2_2") (pintype "passive"))
      (node (ref "U2") (pin "18") (pinfunction "AVCC_18") (pintype "power_in"))
      (node (ref "U2") (pin "4") (pinfunction "VCC_4") (pintype "power_in"))
      (node (ref "U2") (pin "6") (pinfunction "VCC1_6") (pintype "power_in"))
    )
    (net (code "50") (name "V_SENSE") (class "Default")
      (node (ref "R4") (pin "1") (pinfunction "1_1") (pintype "passive"))
      (node (ref "R5") (pin "2") (pinfunction "2_2") (pintype "passive"))
      (node (ref "U2") (pin "23") (pinfunction "(ADC0/PCINT8)PC0_23") (pintype "bidirectional"))
    )
    (net (code "51") (name "unconnected-(IC1-DIN2-Pad10)") (class "Default")
      (node (ref "IC1") (pin "10") (pinfunction "DIN2_10") (pintype "bidirectional"))
    )
    (net (code "52") (name "unconnected-(IC1-DOUT2-Pad7)") (class "Default")
      (node (ref "IC1") (pin "7") (pinfunction "DOUT2_7") (pintype "bidirectional"))
    )
    (net (code "53") (name "unconnected-(IC1-RIN2-Pad8)") (class "Default")
      (node (ref "IC1") (pin "8") (pinfunction "RIN2_8") (pintype "bidirectional"))
    )
    (net (code "54") (name "unconnected-(IC1-ROUT2-Pad9)") (class "Default")
      (node (ref "IC1") (pin "9") (pinfunction "ROUT2_9") (pintype "bidirectional"))
    )
    (net (code "55") (name "unconnected-(IC3-THERMAL_PAD-Pad21)") (class "Default")
      (node (ref "IC3") (pin "21") (pinfunction "THERMAL_PAD_21") (pintype "bidirectional"))
    )
    (net (code "56") (name "unconnected-(U2-(ADC1{slash}PCINT9)PC1-Pad24)") (class "Default")
      (node (ref "U2") (pin "24") (pinfunction "(ADC1/PCINT9)PC1_24") (pintype "bidirectional"))
    )
    (net (code "57") (name "unconnected-(U2-(ADC2{slash}PCINT10)PC2-Pad25)") (class "Default")
      (node (ref "U2") (pin "25") (pinfunction "(ADC2/PCINT10)PC2_25") (pintype "bidirectional"))
    )
    (net (code "58") (name "unconnected-(U2-(ADC3{slash}PCINT11)PC3-Pad26)") (class "Default")
      (node (ref "U2") (pin "26") (pinfunction "(ADC3/PCINT11)PC3_26") (pintype "bidirectional"))
    )
    (net (code "59") (name "unconnected-(U2-ADC6-Pad19)") (class "Default")
      (node (ref "U2") (pin "19") (pinfunction "ADC6_19") (pintype "input"))
    )
    (net (code "60") (name "unconnected-(U2-ADC7-Pad22)") (class "Default")
      (node (ref "U2") (pin "22") (pinfunction "ADC7_22") (pintype "input"))
    )
    (net (code "61") (name "unconnected-(U2-PD3(PCINT19{slash}OC2B{slash}INT1)-Pad1)") (class "Default")
      (node (ref "U2") (pin "1") (pinfunction "PD3(PCINT19/OC2B/INT1)_1") (pintype "bidirectional"))
    )
    (net (code "62") (name "unconnected-(U2-PD4(PCINT20{slash}XCK{slash}T0)-Pad2)") (class "Default")
      (node (ref "U2") (pin "2") (pinfunction "PD4(PCINT20/XCK/T0)_2") (pintype "bidirectional"))
    )
    (net (code "63") (name "unconnected-(U2-PD5(PCINT21{slash}OC0B{slash}T1)-Pad9)") (class "Default")
      (node (ref "U2") (pin "9") (pinfunction "PD5(PCINT21/OC0B/T1)_9") (pintype "bidirectional"))
    )
    (net (code "64") (name "unconnected-(X1A-KL-Pad1)") (class "Default")
      (node (ref "X1") (pin "1") (pinfunction "KL_1") (pintype "passive"))
    )
    (net (code "65") (name "unconnected-(X1B-KL-Pad10)") (class "Default")
      (node (ref "X1") (pin "10") (pinfunction "KL_10") (pintype "passive"))
    )
    (net (code "66") (name "unconnected-(X1E-KL-Pad4)") (class "Default")
      (node (ref "X1") (pin "4") (pinfunction "KL_4") (pintype "passive"))
    )
    (net (code "67") (name "unconnected-(X1G-KL-Pad6)") (class "Default")
      (node (ref "X1") (pin "6") (pinfunction "KL_6") (pintype "passive"))
    )
    (net (code "68") (name "unconnected-(X1H-KL-Pad7)") (class "Default")
      (node (ref "X1") (pin "7") (pinfunction "KL_7") (pintype "passive"))
    )
    (net (code "69") (name "unconnected-(X1I-KL-Pad8)") (class "Default")
      (node (ref "X1") (pin "8") (pinfunction "KL_8") (pintype "passive"))
    )
    (net (code "70") (name "unconnected-(X1J-KL-Pad9)") (class "Default")
      (node (ref "X1") (pin "9") (pinfunction "KL_9") (pintype "passive"))
    )
  )
)
